# current_sense_INA260.net
KiCad netlist of a schematic drawn in EAGLE
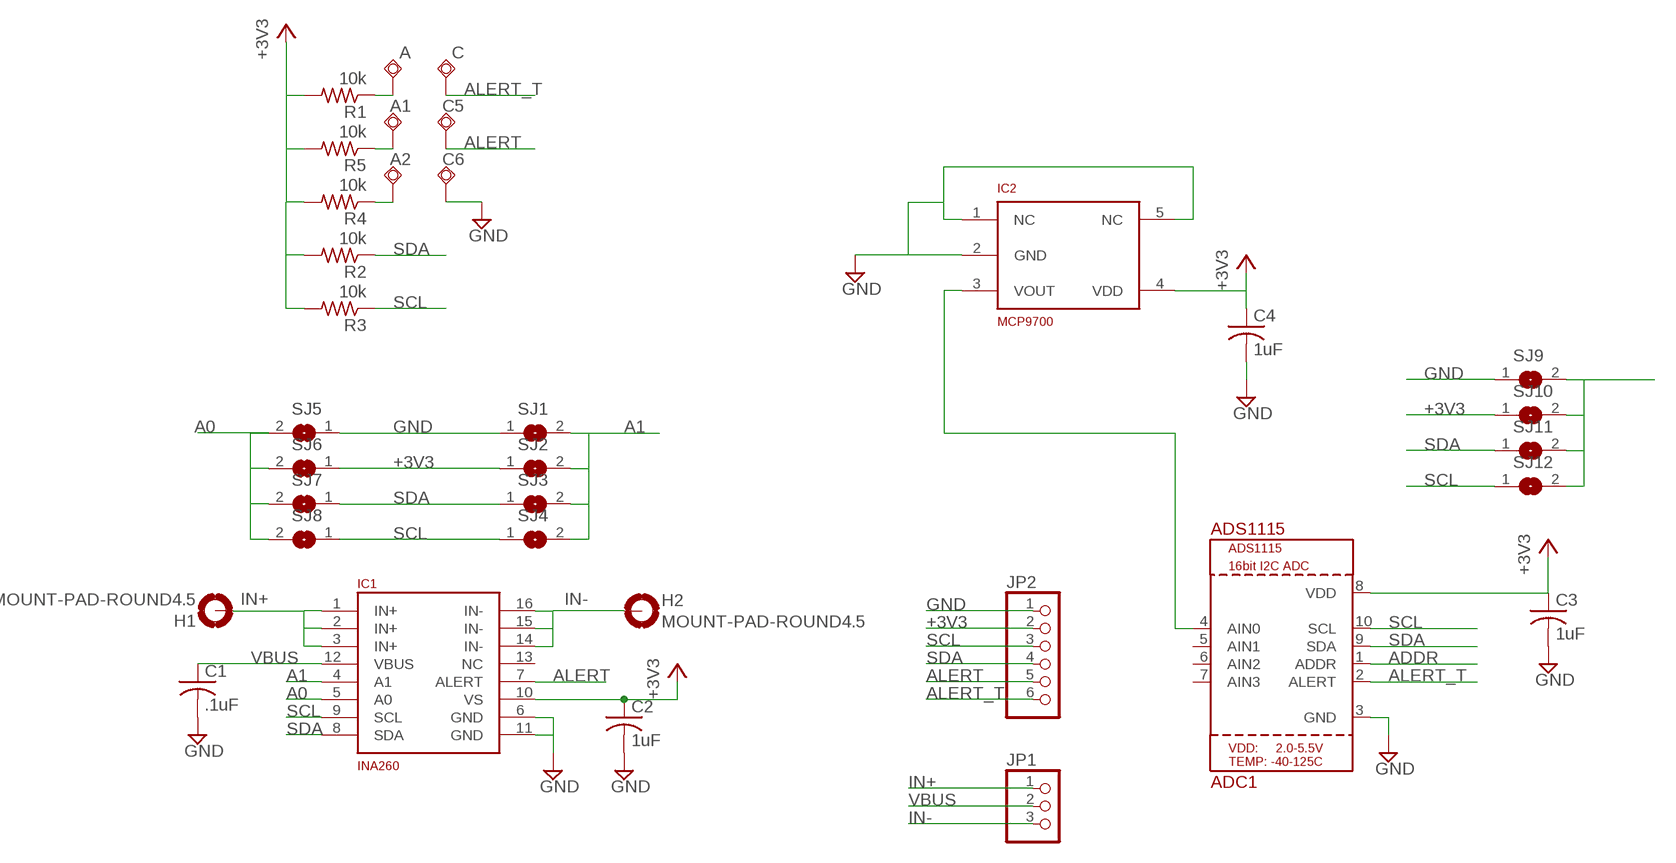
[diagram p0: schematic, sheet 1]

(export (version "E")
  (design (tool "Eeschema 10.0.6"))
  (components
    (comp (ref "A")
      (value "TPSQTP20SQ")
      (footprint "eagle-import:TP20SQ")
      (libsource (lib "eagle-import") (part "TPSQTP20SQ"))
    )
    (comp (ref "A1")
      (value "TPSQTP20SQ")
      (footprint "eagle-import:TP20SQ")
      (libsource (lib "eagle-import") (part "TPSQTP20SQ"))
    )
    (comp (ref "A2")
      (value "TPSQTP20SQ")
      (footprint "eagle-import:TP20SQ")
      (libsource (lib "eagle-import") (part "TPSQTP20SQ"))
    )
    (comp (ref "ADC1")
      (value "ADS1115")
      (footprint "eagle-import:MSOP10")
      (libsource (lib "eagle-import") (part "ADS1115"))
    )
    (comp (ref "C")
      (value "C")
      (footprint "eagle-import:TP20SQ")
      (libsource (lib "eagle-import") (part "TPSQTP20SQ"))
    )
    (comp (ref "C1")
      (value ".1uF")
      (footprint "eagle-import:C0805K")
      (libsource (lib "eagle-import") (part "C-USC0805K"))
    )
    (comp (ref "C2")
      (value "1uF")
      (footprint "eagle-import:C0805K")
      (libsource (lib "eagle-import") (part "C-USC0805K"))
    )
    (comp (ref "C3")
      (value "1uF")
      (footprint "eagle-import:C0805K")
      (libsource (lib "eagle-import") (part "C-USC0805K"))
    )
    (comp (ref "C4")
      (value "1uF")
      (footprint "eagle-import:C0805K")
      (libsource (lib "eagle-import") (part "C-USC0805K"))
    )
    (comp (ref "C5")
      (value "TPSQTP20SQ")
      (footprint "eagle-import:TP20SQ")
      (libsource (lib "eagle-import") (part "TPSQTP20SQ"))
    )
    (comp (ref "C6")
      (value "TPSQTP20SQ")
      (footprint "eagle-import:TP20SQ")
      (libsource (lib "eagle-import") (part "TPSQTP20SQ"))
    )
    (comp (ref "H1")
      (value "MOUNT-PAD-ROUND4.5")
      (footprint "eagle-import:4,5-PAD")
      (libsource (lib "eagle-import") (part "MOUNT-PAD-ROUND4.5"))
    )
    (comp (ref "H2")
      (value "MOUNT-PAD-ROUND4.5")
      (footprint "eagle-import:4,5-PAD")
      (libsource (lib "eagle-import") (part "MOUNT-PAD-ROUND4.5"))
    )
    (comp (ref "IC1")
      (value "INA260")
      (footprint "eagle-import:TSSOP16")
      (libsource (lib "eagle-import") (part "INA260"))
    )
    (comp (ref "IC2")
      (value "MCP9700")
      (footprint "eagle-import:SC70")
      (libsource (lib "eagle-import") (part "MCP9700"))
    )
    (comp (ref "JP1")
      (value "PINHD-1X3")
      (footprint "eagle-import:1X03")
      (libsource (lib "eagle-import") (part "PINHD-1X3"))
    )
    (comp (ref "JP2")
      (value "PINHD-1X6")
      (footprint "eagle-import:1X06")
      (libsource (lib "eagle-import") (part "PINHD-1X6"))
    )
    (comp (ref "R1")
      (value "10k")
      (footprint "eagle-import:R0805")
      (libsource (lib "eagle-import") (part "R-US_R0805"))
    )
    (comp (ref "R2")
      (value "10k")
      (footprint "eagle-import:R0805")
      (libsource (lib "eagle-import") (part "R-US_R0805"))
    )
    (comp (ref "R3")
      (value "10k")
      (footprint "eagle-import:R0805")
      (libsource (lib "eagle-import") (part "R-US_R0805"))
    )
    (comp (ref "R4")
      (value "10k")
      (footprint "eagle-import:R0805")
      (libsource (lib "eagle-import") (part "R-US_R0805"))
    )
    (comp (ref "R5")
      (value "10k")
      (footprint "eagle-import:R0805")
      (libsource (lib "eagle-import") (part "R-US_R0805"))
    )
    (comp (ref "SJ1") (value "SJ") (footprint "eagle-import:SJ") (libsource (lib "eagle-import") (part "SJ")))
    (comp (ref "SJ2") (value "SJ") (footprint "eagle-import:SJ") (libsource (lib "eagle-import") (part "SJ")))
    (comp (ref "SJ3") (value "SJ") (footprint "eagle-import:SJ") (libsource (lib "eagle-import") (part "SJ")))
    (comp (ref "SJ4") (value "SJ") (footprint "eagle-import:SJ") (libsource (lib "eagle-import") (part "SJ")))
    (comp (ref "SJ5") (value "SJ") (footprint "eagle-import:SJ") (libsource (lib "eagle-import") (part "SJ")))
    (comp (ref "SJ6") (value "SJ") (footprint "eagle-import:SJ") (libsource (lib "eagle-import") (part "SJ")))
    (comp (ref "SJ7") (value "SJ") (footprint "eagle-import:SJ") (libsource (lib "eagle-import") (part "SJ")))
    (comp (ref "SJ8") (value "SJ") (footprint "eagle-import:SJ") (libsource (lib "eagle-import") (part "SJ")))
    (comp (ref "SJ9") (value "SJ") (footprint "eagle-import:SJ") (libsource (lib "eagle-import") (part "SJ")))
    (comp (ref "SJ10")
      (value "SJ")
      (footprint "eagle-import:SJ")
      (libsource (lib "eagle-import") (part "SJ"))
    )
    (comp (ref "SJ11")
      (value "SJ")
      (footprint "eagle-import:SJ")
      (libsource (lib "eagle-import") (part "SJ"))
    )
    (comp (ref "SJ12")
      (value "SJ")
      (footprint "eagle-import:SJ")
      (libsource (lib "eagle-import") (part "SJ"))
    )
  )
  (nets
    (net (code "1") (name "+3V3") (class "Default")
      (node (ref "ADC1") (pin "8") (pinfunction "VDD_8") (pintype "bidirectional"))
      (node (ref "C2") (pin "1") (pinfunction "1_1") (pintype "passive"))
      (node (ref "C3") (pin "1") (pinfunction "1_1") (pintype "passive"))
      (node (ref "C4") (pin "1") (pinfunction "1_1") (pintype "passive"))
      (node (ref "IC1") (pin "10") (pinfunction "VS_10") (pintype "bidirectional"))
      (node (ref "IC2") (pin "4") (pinfunction "VDD_4") (pintype "bidirectional"))
      (node (ref "JP2") (pin "2") (pinfunction "2_2") (pintype "passive"))
      (node (ref "R1") (pin "2") (pinfunction "2_2") (pintype "passive"))
      (node (ref "R2") (pin "2") (pinfunction "2_2") (pintype "passive"))
      (node (ref "R3") (pin "2") (pinfunction "2_2") (pintype "passive"))
      (node (ref "R4") (pin "2") (pinfunction "2_2") (pintype "passive"))
      (node (ref "R5") (pin "2") (pinfunction "2_2") (pintype "passive"))
      (node (ref "SJ10") (pin "1") (pinfunction "1_1") (pintype "passive"))
      (node (ref "SJ2") (pin "1") (pinfunction "1_1") (pintype "passive"))
      (node (ref "SJ6") (pin "1") (pinfunction "1_1") (pintype "passive"))
    )
    (net (code "2") (name "/A0") (class "Default")
      (node (ref "IC1") (pin "5") (pinfunction "A0_5") (pintype "bidirectional"))
      (node (ref "SJ5") (pin "2") (pinfunction "2_2") (pintype "passive"))
      (node (ref "SJ6") (pin "2") (pinfunction "2_2") (pintype "passive"))
      (node (ref "SJ7") (pin "2") (pinfunction "2_2") (pintype "passive"))
      (node (ref "SJ8") (pin "2") (pinfunction "2_2") (pintype "passive"))
    )
    (net (code "3") (name "/A1") (class "Default")
      (node (ref "IC1") (pin "4") (pinfunction "A1_4") (pintype "bidirectional"))
      (node (ref "SJ1") (pin "2") (pinfunction "2_2") (pintype "passive"))
      (node (ref "SJ2") (pin "2") (pinfunction "2_2") (pintype "passive"))
      (node (ref "SJ3") (pin "2") (pinfunction "2_2") (pintype "passive"))
      (node (ref "SJ4") (pin "2") (pinfunction "2_2") (pintype "passive"))
    )
    (net (code "4") (name "/ADDR") (class "Default")
      (node (ref "ADC1") (pin "1") (pinfunction "ADDR_1") (pintype "bidirectional"))
      (node (ref "SJ10") (pin "2") (pinfunction "2_2") (pintype "passive"))
      (node (ref "SJ11") (pin "2") (pinfunction "2_2") (pintype "passive"))
      (node (ref "SJ12") (pin "2") (pinfunction "2_2") (pintype "passive"))
      (node (ref "SJ9") (pin "2") (pinfunction "2_2") (pintype "passive"))
    )
    (net (code "5") (name "/ALERT") (class "Default")
      (node (ref "C5") (pin "TP") (pinfunction "TP_TP") (pintype "input"))
      (node (ref "IC1") (pin "7") (pinfunction "ALERT_7") (pintype "bidirectional"))
      (node (ref "JP2") (pin "5") (pinfunction "5_5") (pintype "passive"))
    )
    (net (code "6") (name "/ALERT_T") (class "Default")
      (node (ref "ADC1") (pin "2") (pinfunction "ALERT_2") (pintype "bidirectional"))
      (node (ref "C") (pin "TP") (pinfunction "TP_TP") (pintype "input"))
      (node (ref "JP2") (pin "6") (pinfunction "6_6") (pintype "passive"))
    )
    (net (code "7") (name "/IN+") (class "Default")
      (node (ref "H1") (pin "B4,5") (pinfunction "MOUNT_B4,5") (pintype "passive"))
      (node (ref "IC1") (pin "1") (pinfunction "IN+_1") (pintype "bidirectional"))
      (node (ref "IC1") (pin "2") (pinfunction "IN+_2") (pintype "bidirectional"))
      (node (ref "IC1") (pin "3") (pinfunction "IN+_3") (pintype "bidirectional"))
      (node (ref "JP1") (pin "1") (pinfunction "1_1") (pintype "passive"))
    )
    (net (code "8") (name "/IN-") (class "Default")
      (node (ref "H2") (pin "B4,5") (pinfunction "MOUNT_B4,5") (pintype "passive"))
      (node (ref "IC1") (pin "14") (pinfunction "IN-_14") (pintype "bidirectional"))
      (node (ref "IC1") (pin "15") (pinfunction "IN-_15") (pintype "bidirectional"))
      (node (ref "IC1") (pin "16") (pinfunction "IN-_16") (pintype "bidirectional"))
      (node (ref "JP1") (pin "3") (pinfunction "3_3") (pintype "passive"))
    )
    (net (code "9") (name "/SCL") (class "Default")
      (node (ref "ADC1") (pin "10") (pinfunction "SCL_10") (pintype "bidirectional"))
      (node (ref "IC1") (pin "9") (pinfunction "SCL_9") (pintype "bidirectional"))
      (node (ref "JP2") (pin "3") (pinfunction "3_3") (pintype "passive"))
      (node (ref "R3") (pin "1") (pinfunction "1_1") (pintype "passive"))
      (node (ref "SJ12") (pin "1") (pinfunction "1_1") (pintype "passive"))
      (node (ref "SJ4") (pin "1") (pinfunction "1_1") (pintype "passive"))
      (node (ref "SJ8") (pin "1") (pinfunction "1_1") (pintype "passive"))
    )
    (net (code "10") (name "/SDA") (class "Default")
      (node (ref "ADC1") (pin "9") (pinfunction "SDA_9") (pintype "bidirectional"))
      (node (ref "IC1") (pin "8") (pinfunction "SDA_8") (pintype "bidirectional"))
      (node (ref "JP2") (pin "4") (pinfunction "4_4") (pintype "passive"))
      (node (ref "R2") (pin "1") (pinfunction "1_1") (pintype "passive"))
      (node (ref "SJ11") (pin "1") (pinfunction "1_1") (pintype "passive"))
      (node (ref "SJ3") (pin "1") (pinfunction "1_1") (pintype "passive"))
      (node (ref "SJ7") (pin "1") (pinfunction "1_1") (pintype "passive"))
    )
    (net (code "11") (name "/VBUS") (class "Default")
      (node (ref "C1") (pin "1") (pinfunction "1_1") (pintype "passive"))
      (node (ref "IC1") (pin "12") (pinfunction "VBUS_12") (pintype "bidirectional"))
      (node (ref "JP1") (pin "2") (pinfunction "2_2") (pintype "passive"))
    )
    (net (code "12") (name "GND") (class "Default")
      (node (ref "ADC1") (pin "3") (pinfunction "GND_3") (pintype "bidirectional"))
      (node (ref "C1") (pin "2") (pinfunction "2_2") (pintype "passive"))
      (node (ref "C2") (pin "2") (pinfunction "2_2") (pintype "passive"))
      (node (ref "C3") (pin "2") (pinfunction "2_2") (pintype "passive"))
      (node (ref "C4") (pin "2") (pinfunction "2_2") (pintype "passive"))
      (node (ref "C6") (pin "TP") (pinfunction "TP_TP") (pintype "input"))
      (node (ref "IC1") (pin "11") (pinfunction "GND_11") (pintype "bidirectional"))
      (node (ref "IC1") (pin "6") (pinfunction "GND_6") (pintype "bidirectional"))
      (node (ref "IC2") (pin "1") (pinfunction "NC_1") (pintype "bidirectional"))
      (node (ref "IC2") (pin "2") (pinfunction "GND_2") (pintype "bidirectional"))
      (node (ref "IC2") (pin "5") (pinfunction "NC_5") (pintype "bidirectional"))
      (node (ref "JP2") (pin "1") (pinfunction "1_1") (pintype "passive"))
      (node (ref "SJ1") (pin "1") (pinfunction "1_1") (pintype "passive"))
      (node (ref "SJ5") (pin "1") (pinfunction "1_1") (pintype "passive"))
      (node (ref "SJ9") (pin "1") (pinfunction "1_1") (pintype "passive"))
    )
    (net (code "13") (name "Net-(A-PadTP)") (class "Default")
      (node (ref "A") (pin "TP") (pinfunction "TP_TP") (pintype "input"))
      (node (ref "R1") (pin "1") (pinfunction "1_1") (pintype "passive"))
    )
    (net (code "14") (name "Net-(A1-PadTP)") (class "Default")
      (node (ref "A1") (pin "TP") (pinfunction "TP_TP") (pintype "input"))
      (node (ref "R5") (pin "1") (pinfunction "1_1") (pintype "passive"))
    )
    (net (code "15") (name "Net-(A2-PadTP)") (class "Default")
      (node (ref "A2") (pin "TP") (pinfunction "TP_TP") (pintype "input"))
      (node (ref "R4") (pin "1") (pinfunction "1_1") (pintype "passive"))
    )
    (net (code "16") (name "Net-(ADC1-AIN0)") (class "Default")
      (node (ref "ADC1") (pin "4") (pinfunction "AIN0_4") (pintype "bidirectional"))
      (node (ref "IC2") (pin "3") (pinfunction "VOUT_3") (pintype "bidirectional"))
    )
    (net (code "17") (name "unconnected-(ADC1-AIN1-Pad5)") (class "Default")
      (node (ref "ADC1") (pin "5") (pinfunction "AIN1_5") (pintype "bidirectional"))
    )
    (net (code "18") (name "unconnected-(ADC1-AIN2-Pad6)") (class "Default")
      (node (ref "ADC1") (pin "6") (pinfunction "AIN2_6") (pintype "bidirectional"))
    )
    (net (code "19") (name "unconnected-(ADC1-AIN3-Pad7)") (class "Default")
      (node (ref "ADC1") (pin "7") (pinfunction "AIN3_7") (pintype "bidirectional"))
    )
    (net (code "20") (name "unconnected-(IC1-NC-Pad13)") (class "Default")
      (node (ref "IC1") (pin "13") (pinfunction "NC_13") (pintype "bidirectional"))
    )
  )
)
